# PLL.net
KiCad netlist of a schematic drawn in Altium Designer
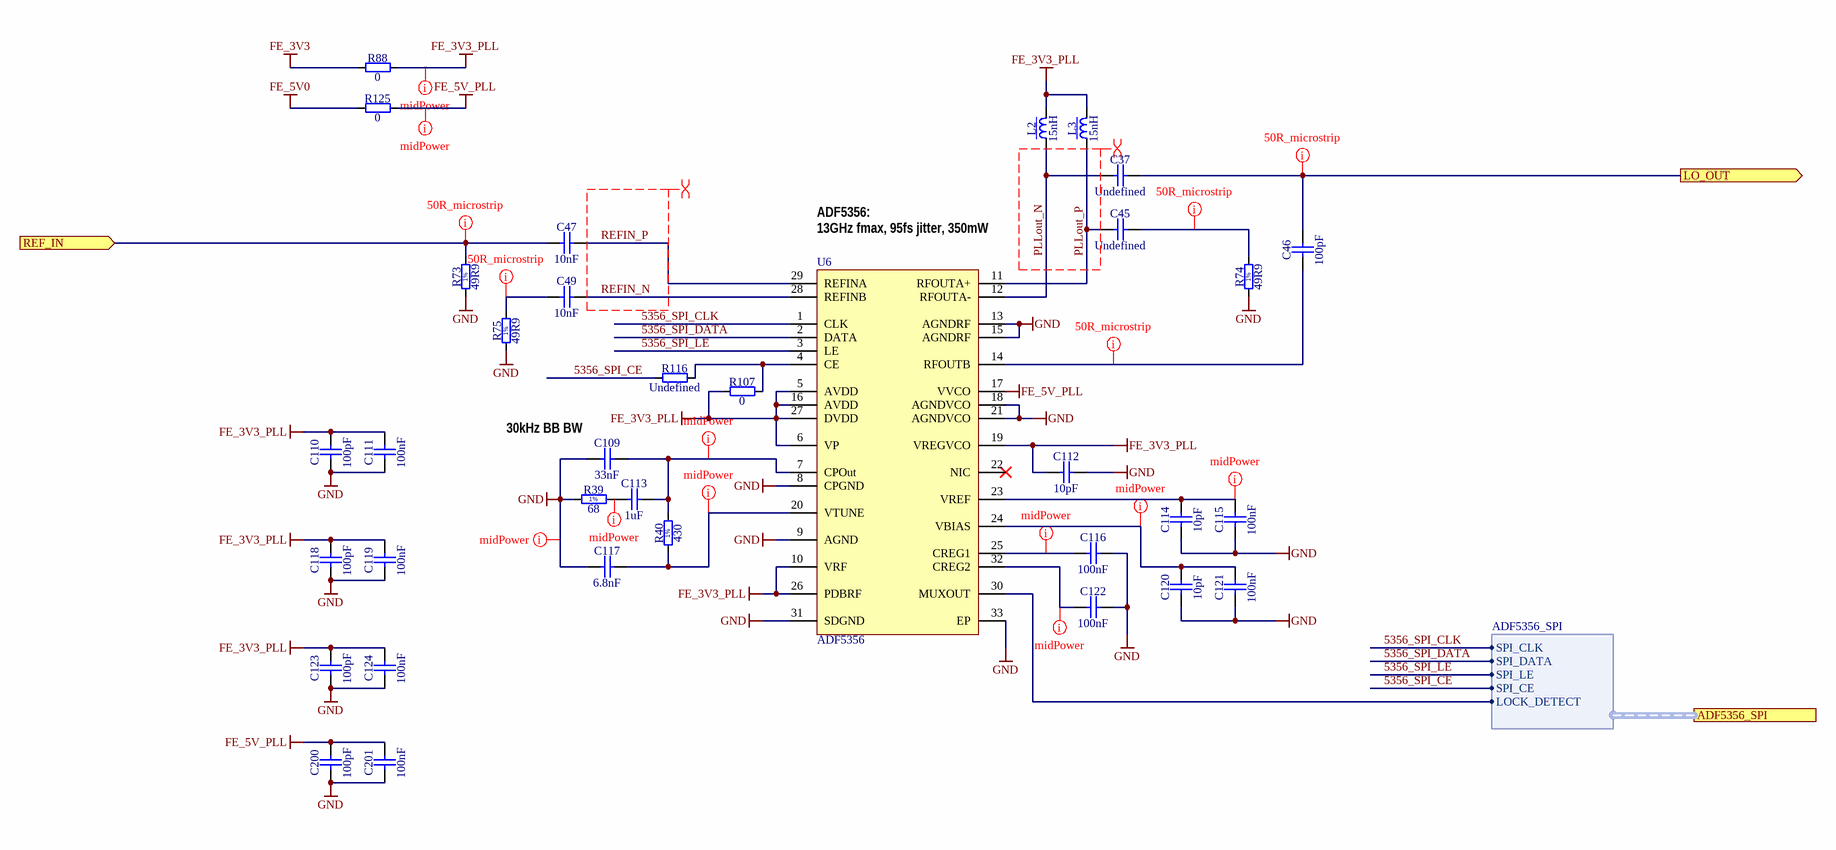
[diagram p0: PLL.SchDoc]

(export (version "E")
  (design (tool "Eeschema 10.0.6"))
  (components
    (comp (ref "C37")
      (value "Undefined")
      (footprint "CAPC1005X55N")
      (description "Non-polarised capacitor")
      (fields (field (name "PART NUMBER") "CC0402_NO-VALUE") (field (name "AUTHOR") "CERN DEM JLC"))
      (libsource (lib "Capacitors") (part "Capacitor - non polarized"))
    )
    (comp (ref "C45")
      (value "Undefined")
      (footprint "CAPC1005X55N")
      (description "Non-polarised capacitor")
      (fields (field (name "PART NUMBER") "CC0402_NO-VALUE") (field (name "AUTHOR") "CERN DEM JLC"))
      (libsource (lib "Capacitors") (part "Capacitor - non polarized"))
    )
    (comp (ref "C46")
      (value "100pF")
      (footprint "CAPC1005X55N")
      (description "Non-polarised capacitor")
      (fields
        (field (name "PART NUMBER") "CC0402_100PF_50V_5%_C0G")
        (field (name "VOLTAGE") "50V")
        (field (name "AUTHOR") "CERN DEM JLC")
      )
      (libsource (lib "Capacitors") (part "Capacitor - non polarized"))
    )
    (comp (ref "C47")
      (value "10nF")
      (footprint "CAPC1005X55N")
      (description "Non-polarised capacitor")
      (fields
        (field (name "PART NUMBER") "CC0402_10NF_50V_10%_X7R")
        (field (name "VOLTAGE") "50V")
        (field (name "AUTHOR") "CERN DEM MR")
      )
      (libsource (lib "Capacitors") (part "Capacitor - non polarized"))
    )
    (comp (ref "C49")
      (value "10nF")
      (footprint "CAPC1005X55N")
      (description "Non-polarised capacitor")
      (fields
        (field (name "PART NUMBER") "CC0402_10NF_50V_10%_X7R")
        (field (name "VOLTAGE") "50V")
        (field (name "AUTHOR") "CERN DEM MR")
      )
      (libsource (lib "Capacitors") (part "Capacitor - non polarized"))
    )
    (comp (ref "C109")
      (value "33nF")
      (footprint "CAPC2012X135N")
      (description "Non-polarised capacitor")
      (fields
        (field (name "PART NUMBER") "CC0805_33NF_25V_10%_X7R")
        (field (name "VOLTAGE") "25V")
        (field (name "AUTHOR") "CERN DEM JLC")
      )
      (libsource (lib "Capacitors") (part "Capacitor - non polarized"))
    )
    (comp (ref "C110")
      (value "100pF")
      (footprint "CAPC1005X55N")
      (description "Non-polarised capacitor")
      (fields
        (field (name "PART NUMBER") "CC0402_100PF_50V_5%_C0G")
        (field (name "VOLTAGE") "50V")
        (field (name "AUTHOR") "CERN DEM JLC")
      )
      (libsource (lib "Capacitors") (part "Capacitor - non polarized"))
    )
    (comp (ref "C111")
      (value "100nF")
      (footprint "CAPC1005X55N")
      (description "Non-polarised capacitor")
      (fields
        (field (name "PART NUMBER") "CC0402_100NF_50V_10%_X7R")
        (field (name "VOLTAGE") "50V")
        (field (name "AUTHOR") "CERN DEM MR")
      )
      (libsource (lib "Capacitors") (part "Capacitor - non polarized"))
    )
    (comp (ref "C112")
      (value "10pF")
      (footprint "CAPC1005X55N")
      (description "Non-polarised capacitor")
      (fields
        (field (name "PART NUMBER") "CC0402_10PF_50V_5%_C0G")
        (field (name "VOLTAGE") "50V")
        (field (name "AUTHOR") "CERN DEM JLC")
      )
      (libsource (lib "Capacitors") (part "Capacitor - non polarized"))
    )
    (comp (ref "C113")
      (value "1uF")
      (footprint "CAPC3216X140N")
      (description "Non-polarised capacitor")
      (fields
        (field (name "PART NUMBER") "CC1206_1UF_25V_10%_X7R")
        (field (name "VOLTAGE") "25V")
        (field (name "AUTHOR") "CERN DEM JLC")
      )
      (libsource (lib "Capacitors") (part "Capacitor - non polarized"))
    )
    (comp (ref "C114")
      (value "10pF")
      (footprint "CAPC1005X55N")
      (description "Non-polarised capacitor")
      (fields
        (field (name "PART NUMBER") "CC0402_10PF_50V_5%_C0G")
        (field (name "VOLTAGE") "50V")
        (field (name "AUTHOR") "CERN DEM JLC")
      )
      (libsource (lib "Capacitors") (part "Capacitor - non polarized"))
    )
    (comp (ref "C115")
      (value "100nF")
      (footprint "CAPC1005X55N")
      (description "Non-polarised capacitor")
      (fields
        (field (name "PART NUMBER") "CC0402_100NF_50V_10%_X7R")
        (field (name "VOLTAGE") "50V")
        (field (name "AUTHOR") "CERN DEM MR")
      )
      (libsource (lib "Capacitors") (part "Capacitor - non polarized"))
    )
    (comp (ref "C116")
      (value "100nF")
      (footprint "CAPC1005X55N")
      (description "Non-polarised capacitor")
      (fields
        (field (name "PART NUMBER") "CC0402_100NF_50V_10%_X7R")
        (field (name "VOLTAGE") "50V")
        (field (name "AUTHOR") "CERN DEM MR")
      )
      (libsource (lib "Capacitors") (part "Capacitor - non polarized"))
    )
    (comp (ref "C117")
      (value "6.8nF")
      (footprint "CAPC2012X135N")
      (description "Non-polarised capacitor")
      (fields
        (field (name "PART NUMBER") "CC0805_6.8NF_50V_10%_X7R")
        (field (name "VOLTAGE") "50V")
        (field (name "AUTHOR") "CERN DEM JLC")
      )
      (libsource (lib "Capacitors") (part "Capacitor - non polarized"))
    )
    (comp (ref "C118")
      (value "100pF")
      (footprint "CAPC1005X55N")
      (description "Non-polarised capacitor")
      (fields
        (field (name "PART NUMBER") "CC0402_100PF_50V_5%_C0G")
        (field (name "VOLTAGE") "50V")
        (field (name "AUTHOR") "CERN DEM JLC")
      )
      (libsource (lib "Capacitors") (part "Capacitor - non polarized"))
    )
    (comp (ref "C119")
      (value "100nF")
      (footprint "CAPC1005X55N")
      (description "Non-polarised capacitor")
      (fields
        (field (name "PART NUMBER") "CC0402_100NF_50V_10%_X7R")
        (field (name "VOLTAGE") "50V")
        (field (name "AUTHOR") "CERN DEM MR")
      )
      (libsource (lib "Capacitors") (part "Capacitor - non polarized"))
    )
    (comp (ref "C120")
      (value "10pF")
      (footprint "CAPC1005X55N")
      (description "Non-polarised capacitor")
      (fields
        (field (name "PART NUMBER") "CC0402_10PF_50V_5%_C0G")
        (field (name "VOLTAGE") "50V")
        (field (name "AUTHOR") "CERN DEM JLC")
      )
      (libsource (lib "Capacitors") (part "Capacitor - non polarized"))
    )
    (comp (ref "C121")
      (value "100nF")
      (footprint "CAPC1005X55N")
      (description "Non-polarised capacitor")
      (fields
        (field (name "PART NUMBER") "CC0402_100NF_50V_10%_X7R")
        (field (name "VOLTAGE") "50V")
        (field (name "AUTHOR") "CERN DEM MR")
      )
      (libsource (lib "Capacitors") (part "Capacitor - non polarized"))
    )
    (comp (ref "C122")
      (value "100nF")
      (footprint "CAPC1005X55N")
      (description "Non-polarised capacitor")
      (fields
        (field (name "PART NUMBER") "CC0402_100NF_50V_10%_X7R")
        (field (name "VOLTAGE") "50V")
        (field (name "AUTHOR") "CERN DEM MR")
      )
      (libsource (lib "Capacitors") (part "Capacitor - non polarized"))
    )
    (comp (ref "C123")
      (value "100pF")
      (footprint "CAPC1005X55N")
      (description "Non-polarised capacitor")
      (fields
        (field (name "PART NUMBER") "CC0402_100PF_50V_5%_C0G")
        (field (name "VOLTAGE") "50V")
        (field (name "AUTHOR") "CERN DEM JLC")
      )
      (libsource (lib "Capacitors") (part "Capacitor - non polarized"))
    )
    (comp (ref "C124")
      (value "100nF")
      (footprint "CAPC1005X55N")
      (description "Non-polarised capacitor")
      (fields
        (field (name "PART NUMBER") "CC0402_100NF_50V_10%_X7R")
        (field (name "VOLTAGE") "50V")
        (field (name "AUTHOR") "CERN DEM MR")
      )
      (libsource (lib "Capacitors") (part "Capacitor - non polarized"))
    )
    (comp (ref "C200")
      (value "100pF")
      (footprint "CAPC1005X55N")
      (description "Non-polarised capacitor")
      (fields
        (field (name "PART NUMBER") "CC0402_100PF_50V_5%_C0G")
        (field (name "VOLTAGE") "50V")
        (field (name "AUTHOR") "CERN DEM JLC")
      )
      (libsource (lib "Capacitors") (part "Capacitor - non polarized"))
    )
    (comp (ref "C201")
      (value "100nF")
      (footprint "CAPC1005X55N")
      (description "Non-polarised capacitor")
      (fields
        (field (name "PART NUMBER") "CC0402_100NF_50V_10%_X7R")
        (field (name "VOLTAGE") "50V")
        (field (name "AUTHOR") "CERN DEM MR")
      )
      (libsource (lib "Capacitors") (part "Capacitor - non polarized"))
    )
    (comp (ref "L2")
      (value "15nH")
      (footprint "IND_COILCRAFT_0402DC")
      (description "Inductor With Core")
      (fields
        (field (name "PART NUMBER") "IND0402_15NH_2%_COILCRAFT_0402DC")
        (field (name "POWER") "1A")
        (field (name "AUTHOR") "CERN DEM JLC")
      )
      (libsource (lib "Inductors & Transformers") (part "Inductor With Magnetic core"))
    )
    (comp (ref "L3")
      (value "15nH")
      (footprint "IND_COILCRAFT_0402DC")
      (description "Inductor With Core")
      (fields
        (field (name "PART NUMBER") "IND0402_15NH_2%_COILCRAFT_0402DC")
        (field (name "POWER") "1A")
        (field (name "AUTHOR") "CERN DEM JLC")
      )
      (libsource (lib "Inductors & Transformers") (part "Inductor With Magnetic core"))
    )
    (comp (ref "R39")
      (value "68")
      (footprint "RESC1608X55N")
      (description "Resistor - 1%")
      (fields
        (field (name "PART NUMBER") "R0603_68R_1%_0.1W_100PPM")
        (field (name "POWER") "0.1W")
        (field (name "AUTHOR") "CERN DEM JLC")
      )
      (libsource (lib "Resistors") (part "Resistor - 1%"))
    )
    (comp (ref "R40")
      (value "430")
      (footprint "RESC1608X55N")
      (description "Resistor - 1%")
      (fields
        (field (name "PART NUMBER") "R0603_430R_1%_0.1W_100PPM")
        (field (name "POWER") "0.1W")
        (field (name "AUTHOR") "CERN DEM JLC")
      )
      (libsource (lib "Resistors") (part "Resistor - 1%"))
    )
    (comp (ref "R73")
      (value "49R9")
      (footprint "RESC1005X40N")
      (description "Resistor - 1%")
      (fields
        (field (name "PART NUMBER") "R0402_49R9_1%_0.0625W_100PPM")
        (field (name "POWER") "0.0625W")
        (field (name "AUTHOR") "CERN DEM JLC")
      )
      (libsource (lib "Resistors") (part "Resistor - 1%"))
    )
    (comp (ref "R74")
      (value "49R9")
      (footprint "RESC1005X40N")
      (description "Resistor - 1%")
      (fields
        (field (name "PART NUMBER") "R0402_49R9_1%_0.0625W_100PPM")
        (field (name "POWER") "0.0625W")
        (field (name "AUTHOR") "CERN DEM JLC")
      )
      (libsource (lib "Resistors") (part "Resistor - 1%"))
    )
    (comp (ref "R75")
      (value "49R9")
      (footprint "RESC1005X40N")
      (description "Resistor - 1%")
      (fields
        (field (name "PART NUMBER") "R0402_49R9_1%_0.0625W_100PPM")
        (field (name "POWER") "0.0625W")
        (field (name "AUTHOR") "CERN DEM JLC")
      )
      (libsource (lib "Resistors") (part "Resistor - 1%"))
    )
    (comp (ref "R88")
      (value "0")
      (footprint "RESC1608X55N")
      (description "Resistor")
      (fields
        (field (name "PART NUMBER") "R0603_0R_JUMPER")
        (field (name "MANUFACTURER") "GENERIC")
        (field (name "AUTHOR") "CERN DEM JLC")
      )
      (libsource (lib "Resistors") (part "Resistor"))
    )
    (comp (ref "R107")
      (value "0")
      (footprint "RESC1005X40N")
      (description "Resistor")
      (fields
        (field (name "PART NUMBER") "R0402_0R_JUMPER")
        (field (name "MANUFACTURER") "GENERIC")
        (field (name "AUTHOR") "CERN DEM JLC")
      )
      (libsource (lib "Resistors") (part "Resistor"))
    )
    (comp (ref "R116")
      (value "Undefined")
      (footprint "RESC1005X40N")
      (description "Resistor")
      (fields (field (name "PART NUMBER") "R0402_NO-VALUE") (field (name "AUTHOR") "CERN DEM JLC"))
      (libsource (lib "Resistors") (part "Resistor"))
    )
    (comp (ref "R125")
      (value "0")
      (footprint "RESC1608X55N")
      (description "Resistor")
      (fields
        (field (name "PART NUMBER") "R0603_0R_JUMPER")
        (field (name "MANUFACTURER") "GENERIC")
        (field (name "AUTHOR") "CERN DEM JLC")
      )
      (libsource (lib "Resistors") (part "Resistor"))
    )
    (comp (ref "U6") (value "ADF5356") (footprint "ADF3356") (libsource (lib "FMC_SDR") (part "ADF5356")))
  )
  (nets
    (net (code "2") (name "/5356_SPI_CE") (class "Default")
      (node (ref "R116") (pin "1") (pinfunction "1_1") (pintype "passive"))
    )
    (net (code "3") (name "/5356_SPI_CLK") (class "Default")
      (node (ref "U6") (pin "1") (pinfunction "CLK_1") (pintype "passive"))
    )
    (net (code "4") (name "/5356_SPI_DATA") (class "Default")
      (node (ref "U6") (pin "2") (pinfunction "DATA_2") (pintype "passive"))
    )
    (net (code "5") (name "/5356_SPI_LE") (class "Default")
      (node (ref "U6") (pin "3") (pinfunction "LE_3") (pintype "passive"))
    )
    (net (code "6") (name "/LOCK_DETECT") (class "Default")
      (node (ref "U6") (pin "30") (pinfunction "MUXOUT_30") (pintype "passive"))
    )
    (net (code "7") (name "/LO_OUT") (class "Default")
      (node (ref "C37") (pin "2") (pinfunction "2_2") (pintype "passive"))
      (node (ref "C46") (pin "2") (pinfunction "2_2") (pintype "passive"))
    )
    (net (code "8") (name "/PLLout_N") (class "Default")
      (node (ref "C37") (pin "1") (pinfunction "1_1") (pintype "passive"))
      (node (ref "L2") (pin "1") (pinfunction "1_1") (pintype "passive"))
      (node (ref "U6") (pin "12") (pinfunction "RFOUTA-_12") (pintype "passive"))
    )
    (net (code "9") (name "/PLLout_P") (class "Default")
      (node (ref "C45") (pin "1") (pinfunction "1_1") (pintype "passive"))
      (node (ref "L3") (pin "1") (pinfunction "1_1") (pintype "passive"))
      (node (ref "U6") (pin "11") (pinfunction "RFOUTA+_11") (pintype "passive"))
    )
    (net (code "10") (name "/REFIN_N") (class "Default")
      (node (ref "C49") (pin "2") (pinfunction "2_2") (pintype "passive"))
      (node (ref "U6") (pin "28") (pinfunction "REFINB_28") (pintype "passive"))
    )
    (net (code "11") (name "/REFIN_P") (class "Default")
      (node (ref "C47") (pin "2") (pinfunction "2_2") (pintype "passive"))
      (node (ref "U6") (pin "29") (pinfunction "REFINA_29") (pintype "passive"))
    )
    (net (code "12") (name "/REF_IN") (class "Default")
      (node (ref "C47") (pin "1") (pinfunction "1_1") (pintype "passive"))
      (node (ref "R73") (pin "2") (pinfunction "2_2") (pintype "passive"))
    )
    (net (code "14") (name "FE_3V3") (class "Default")
      (node (ref "R88") (pin "1") (pinfunction "1_1") (pintype "passive"))
    )
    (net (code "15") (name "FE_3V3_PLL") (class "Default")
      (node (ref "C110") (pin "2") (pinfunction "2_2") (pintype "passive"))
      (node (ref "C111") (pin "2") (pinfunction "2_2") (pintype "passive"))
      (node (ref "C112") (pin "1") (pinfunction "1_1") (pintype "passive"))
      (node (ref "C118") (pin "2") (pinfunction "2_2") (pintype "passive"))
      (node (ref "C119") (pin "2") (pinfunction "2_2") (pintype "passive"))
      (node (ref "C123") (pin "2") (pinfunction "2_2") (pintype "passive"))
      (node (ref "C124") (pin "2") (pinfunction "2_2") (pintype "passive"))
      (node (ref "L2") (pin "2") (pinfunction "2_2") (pintype "passive"))
      (node (ref "L3") (pin "2") (pinfunction "2_2") (pintype "passive"))
      (node (ref "R107") (pin "1") (pinfunction "1_1") (pintype "passive"))
      (node (ref "R88") (pin "2") (pinfunction "2_2") (pintype "passive"))
      (node (ref "U6") (pin "10") (pinfunction "VRF_10") (pintype "passive"))
      (node (ref "U6") (pin "16") (pinfunction "AVDD_16") (pintype "passive"))
      (node (ref "U6") (pin "19") (pinfunction "VREGVCO_19") (pintype "passive"))
      (node (ref "U6") (pin "26") (pinfunction "PDBRF_26") (pintype "passive"))
      (node (ref "U6") (pin "27") (pinfunction "DVDD_27") (pintype "passive"))
      (node (ref "U6") (pin "5") (pinfunction "AVDD_5") (pintype "passive"))
      (node (ref "U6") (pin "6") (pinfunction "VP_6") (pintype "passive"))
    )
    (net (code "16") (name "FE_5V0") (class "Default")
      (node (ref "R125") (pin "1") (pinfunction "1_1") (pintype "passive"))
    )
    (net (code "17") (name "FE_5V_PLL") (class "Default")
      (node (ref "C200") (pin "2") (pinfunction "2_2") (pintype "passive"))
      (node (ref "C201") (pin "2") (pinfunction "2_2") (pintype "passive"))
      (node (ref "R125") (pin "2") (pinfunction "2_2") (pintype "passive"))
      (node (ref "U6") (pin "17") (pinfunction "VVCO_17") (pintype "passive"))
    )
    (net (code "18") (name "GND") (class "Default")
      (node (ref "C109") (pin "1") (pinfunction "1_1") (pintype "passive"))
      (node (ref "C110") (pin "1") (pinfunction "1_1") (pintype "passive"))
      (node (ref "C111") (pin "1") (pinfunction "1_1") (pintype "passive"))
      (node (ref "C112") (pin "2") (pinfunction "2_2") (pintype "passive"))
      (node (ref "C114") (pin "1") (pinfunction "1_1") (pintype "passive"))
      (node (ref "C115") (pin "1") (pinfunction "1_1") (pintype "passive"))
      (node (ref "C116") (pin "2") (pinfunction "2_2") (pintype "passive"))
      (node (ref "C117") (pin "1") (pinfunction "1_1") (pintype "passive"))
      (node (ref "C118") (pin "1") (pinfunction "1_1") (pintype "passive"))
      (node (ref "C119") (pin "1") (pinfunction "1_1") (pintype "passive"))
      (node (ref "C120") (pin "1") (pinfunction "1_1") (pintype "passive"))
      (node (ref "C121") (pin "1") (pinfunction "1_1") (pintype "passive"))
      (node (ref "C122") (pin "2") (pinfunction "2_2") (pintype "passive"))
      (node (ref "C123") (pin "1") (pinfunction "1_1") (pintype "passive"))
      (node (ref "C124") (pin "1") (pinfunction "1_1") (pintype "passive"))
      (node (ref "C200") (pin "1") (pinfunction "1_1") (pintype "passive"))
      (node (ref "C201") (pin "1") (pinfunction "1_1") (pintype "passive"))
      (node (ref "R39") (pin "1") (pinfunction "1_1") (pintype "passive"))
      (node (ref "R73") (pin "1") (pinfunction "1_1") (pintype "passive"))
      (node (ref "R74") (pin "1") (pinfunction "1_1") (pintype "passive"))
      (node (ref "R75") (pin "1") (pinfunction "1_1") (pintype "passive"))
      (node (ref "U6") (pin "13") (pinfunction "AGNDRF_13") (pintype "passive"))
      (node (ref "U6") (pin "15") (pinfunction "AGNDRF_15") (pintype "passive"))
      (node (ref "U6") (pin "18") (pinfunction "AGNDVCO_18") (pintype "passive"))
      (node (ref "U6") (pin "21") (pinfunction "AGNDVCO_21") (pintype "passive"))
      (node (ref "U6") (pin "31") (pinfunction "SDGND_31") (pintype "passive"))
      (node (ref "U6") (pin "33") (pinfunction "EP_33") (pintype "passive"))
      (node (ref "U6") (pin "8") (pinfunction "CPGND_8") (pintype "passive"))
      (node (ref "U6") (pin "9") (pinfunction "AGND_9") (pintype "passive"))
    )
    (net (code "19") (name "Net-(C45-Pad2)") (class "Default")
      (node (ref "C45") (pin "2") (pinfunction "2_2") (pintype "passive"))
      (node (ref "R74") (pin "2") (pinfunction "2_2") (pintype "passive"))
    )
    (net (code "20") (name "Net-(C49-Pad1)") (class "Default")
      (node (ref "C49") (pin "1") (pinfunction "1_1") (pintype "passive"))
      (node (ref "R75") (pin "2") (pinfunction "2_2") (pintype "passive"))
    )
    (net (code "21") (name "Net-(C113-Pad1)") (class "Default")
      (node (ref "C113") (pin "1") (pinfunction "1_1") (pintype "passive"))
      (node (ref "R39") (pin "2") (pinfunction "2_2") (pintype "passive"))
    )
    (net (code "22") (name "Net-(U6-CE)") (class "Default")
      (node (ref "R107") (pin "2") (pinfunction "2_2") (pintype "passive"))
      (node (ref "R116") (pin "2") (pinfunction "2_2") (pintype "passive"))
      (node (ref "U6") (pin "4") (pinfunction "CE_4") (pintype "passive"))
    )
    (net (code "23") (name "Net-(U6-CPOut)") (class "Default")
      (node (ref "C109") (pin "2") (pinfunction "2_2") (pintype "passive"))
      (node (ref "C113") (pin "2") (pinfunction "2_2") (pintype "passive"))
      (node (ref "R40") (pin "2") (pinfunction "2_2") (pintype "passive"))
      (node (ref "U6") (pin "7") (pinfunction "CPOut_7") (pintype "passive"))
    )
    (net (code "24") (name "Net-(U6-CREG1)") (class "Default")
      (node (ref "C116") (pin "1") (pinfunction "1_1") (pintype "passive"))
      (node (ref "U6") (pin "25") (pinfunction "CREG1_25") (pintype "passive"))
    )
    (net (code "25") (name "Net-(U6-CREG2)") (class "Default")
      (node (ref "C122") (pin "1") (pinfunction "1_1") (pintype "passive"))
      (node (ref "U6") (pin "32") (pinfunction "CREG2_32") (pintype "passive"))
    )
    (net (code "26") (name "Net-(U6-RFOUTB)") (class "Default")
      (node (ref "C46") (pin "1") (pinfunction "1_1") (pintype "passive"))
      (node (ref "U6") (pin "14") (pinfunction "RFOUTB_14") (pintype "passive"))
    )
    (net (code "27") (name "Net-(U6-VBIAS)") (class "Default")
      (node (ref "C120") (pin "2") (pinfunction "2_2") (pintype "passive"))
      (node (ref "C121") (pin "2") (pinfunction "2_2") (pintype "passive"))
      (node (ref "U6") (pin "24") (pinfunction "VBIAS_24") (pintype "passive"))
    )
    (net (code "28") (name "Net-(U6-VREF)") (class "Default")
      (node (ref "C114") (pin "2") (pinfunction "2_2") (pintype "passive"))
      (node (ref "C115") (pin "2") (pinfunction "2_2") (pintype "passive"))
      (node (ref "U6") (pin "23") (pinfunction "VREF_23") (pintype "passive"))
    )
    (net (code "29") (name "Net-(U6-VTUNE)") (class "Default")
      (node (ref "C117") (pin "2") (pinfunction "2_2") (pintype "passive"))
      (node (ref "R40") (pin "1") (pinfunction "1_1") (pintype "passive"))
      (node (ref "U6") (pin "20") (pinfunction "VTUNE_20") (pintype "passive"))
    )
    (net (code "30") (name "unconnected-(U6-NIC-Pad22)") (class "Default")
      (node (ref "U6") (pin "22") (pinfunction "NIC_22") (pintype "passive+no_connect"))
    )
  )
)
